# 01_-_POWER.net
KiCad netlist of a schematic drawn in Altium Designer
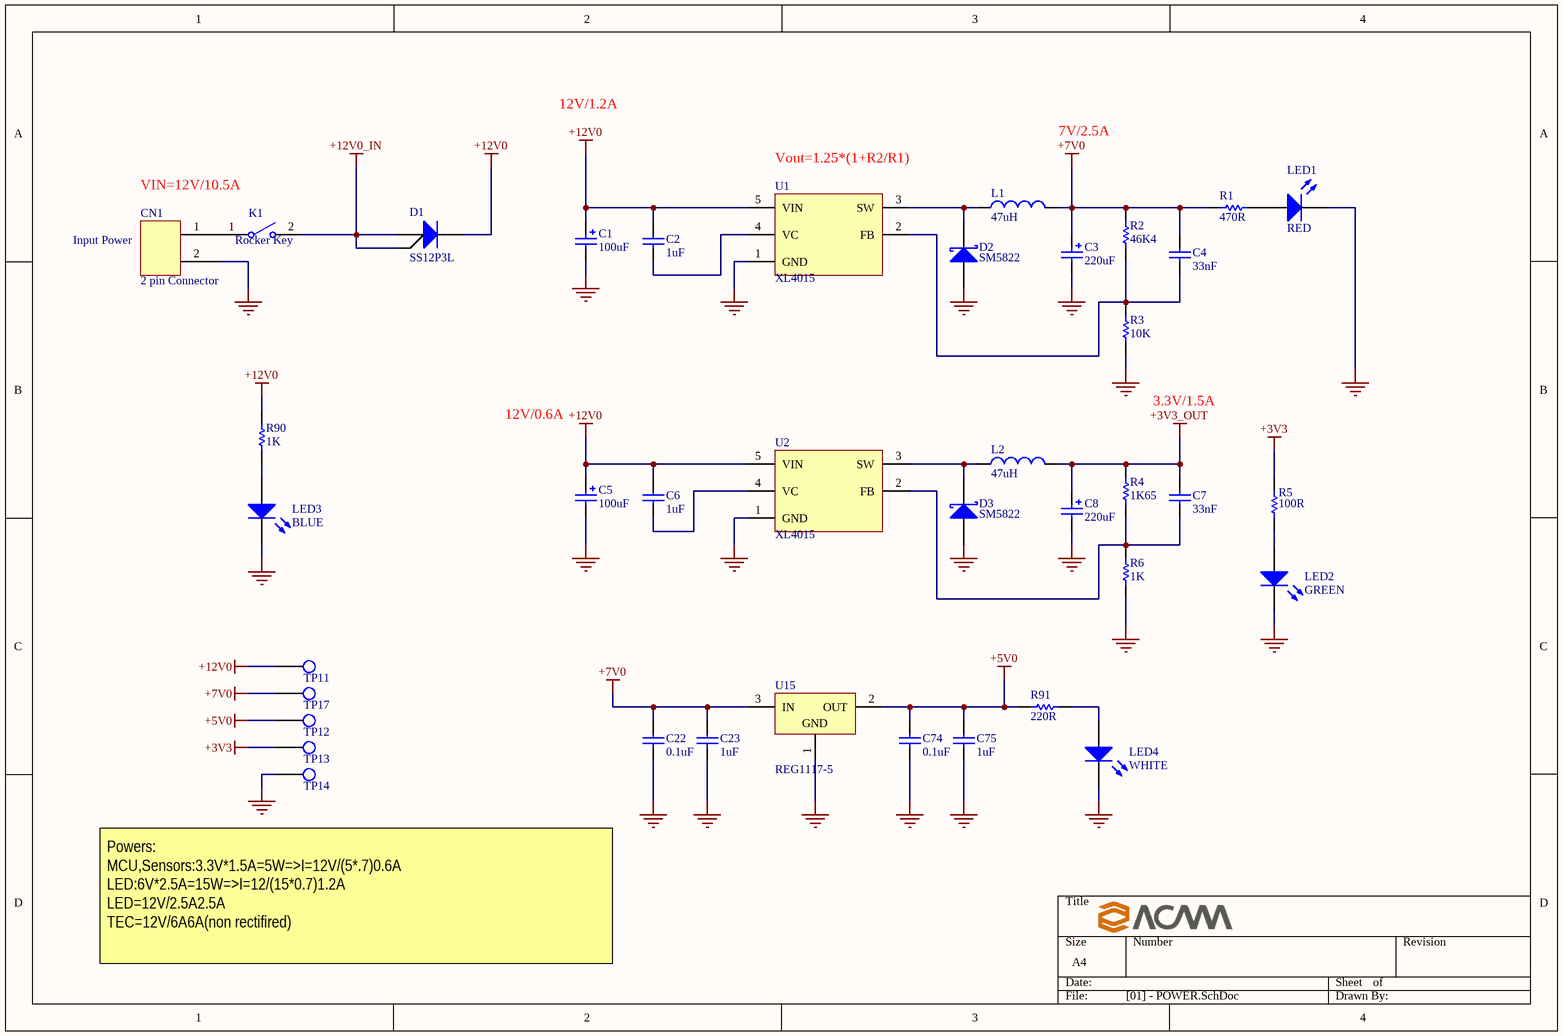
[diagram p0: [01] - POWER.SchDoc]

(export (version "E")
  (design (tool "Eeschema 10.0.6"))
  (components
    (comp (ref "C1")
      (value "100uF")
      (footprint "WCAP-ASLI_6.3x5.5")
      (description "Aluminium Electrolytic Capacitor")
      (libsource (lib "Farzan Custom Library") (part "Cap Aluminium Electrolytic"))
    )
    (comp (ref "C2")
      (value "1uF")
      (footprint "0805_C_AUTO")
      (description "Non-Pol SMD Capacitor")
      (libsource (lib "Farzan Custom Library") (part "Cap SMD"))
    )
    (comp (ref "C3")
      (value "220uF")
      (footprint "WCAP-ASLI_6.3x5.5")
      (description "Aluminium Electrolytic Capacitor")
      (libsource (lib "Farzan Custom Library") (part "Cap Aluminium Electrolytic"))
    )
    (comp (ref "C4")
      (value "33nF")
      (footprint "0805_C_AUTO")
      (description "Non-Pol SMD Capacitor")
      (libsource (lib "Farzan Custom Library") (part "Cap SMD"))
    )
    (comp (ref "C5")
      (value "100uF")
      (footprint "WCAP-ASLI_6.3x5.5")
      (description "Aluminium Electrolytic Capacitor")
      (libsource (lib "Farzan Custom Library") (part "Cap Aluminium Electrolytic"))
    )
    (comp (ref "C6")
      (value "1uF")
      (footprint "0805_C_AUTO")
      (description "Non-Pol SMD Capacitor")
      (libsource (lib "Farzan Custom Library") (part "Cap SMD"))
    )
    (comp (ref "C7")
      (value "33nF")
      (footprint "0805_C_AUTO")
      (description "Non-Pol SMD Capacitor")
      (libsource (lib "Farzan Custom Library") (part "Cap SMD"))
    )
    (comp (ref "C8")
      (value "220uF")
      (footprint "WCAP-ASLI_6.3x5.5")
      (description "Aluminium Electrolytic Capacitor")
      (libsource (lib "Farzan Custom Library") (part "Cap Aluminium Electrolytic"))
    )
    (comp (ref "C22")
      (value "0.1uF")
      (footprint "0805_C_AUTO")
      (description "Non-Pol SMD Capacitor")
      (libsource (lib "Farzan Custom Library") (part "Cap SMD"))
    )
    (comp (ref "C23")
      (value "1uF")
      (footprint "0805_C_AUTO")
      (description "Non-Pol SMD Capacitor")
      (libsource (lib "Farzan Custom Library") (part "Cap SMD"))
    )
    (comp (ref "C74")
      (value "0.1uF")
      (footprint "0805_C_AUTO")
      (description "Non-Pol SMD Capacitor")
      (libsource (lib "Farzan Custom Library") (part "Cap SMD"))
    )
    (comp (ref "C75")
      (value "1uF")
      (footprint "0805_C_AUTO")
      (description "Non-Pol SMD Capacitor")
      (libsource (lib "Farzan Custom Library") (part "Cap SMD"))
    )
    (comp (ref "CN1")
      (value "2 pin Connector")
      (footprint "KF142R_CONN_2PIN")
      (description "KAIFENG Screwless Connector 2 pin")
      (fields (field (name "MANUFACTURER PART NUM") "KF142R"))
      (libsource (lib "Farzan Custom Library") (part "Connector Screwless 2 pin"))
    )
    (comp (ref "D1")
      (value "SS12P3L")
      (footprint "TO-277A")
      (description "High Current Density Surface Mount Schottky Barrier Rectifiers")
      (fields (field (name "MANUFACTURER PART NUM") "SS12P3LHM3_A/H"))
      (libsource (lib "Farzan Custom Library") (part "Diode dual"))
    )
    (comp (ref "D2")
      (value "SM5822")
      (footprint "DO-214AB")
      (description "Schottky Diode")
      (libsource (lib "Farzan Custom Library") (part "Diode Schottky"))
    )
    (comp (ref "D3")
      (value "SM5822")
      (footprint "DO-214AB")
      (description "Schottky Diode")
      (libsource (lib "Farzan Custom Library") (part "Diode Schottky"))
    )
    (comp (ref "K1")
      (value "Rocker Key")
      (footprint "MR-1-116")
      (fields (field (name "MANUFACTURER PART NUM") "MR-1-116-C5N-BB"))
      (libsource (lib "Farzan Custom Library") (part "Rocker Key"))
    )
    (comp (ref "L1")
      (value "47uH")
      (footprint "INDUCTOR_12x12")
      (description "Inductor SMD")
      (fields (field (name "MANUFACTURER PART NUM") "MSS1210-473MED"))
      (libsource (lib "Farzan Custom Library") (part "Inductor"))
    )
    (comp (ref "L2")
      (value "47uH")
      (footprint "INDUCTOR_12x12")
      (description "Inductor SMD")
      (fields (field (name "MANUFACTURER PART NUM") "MSS1210-473MED"))
      (libsource (lib "Farzan Custom Library") (part "Inductor"))
    )
    (comp (ref "LED1")
      (value "RED")
      (footprint "LED_1206")
      (description "Typical LED")
      (libsource (lib "Farzan Custom Library") (part "LED"))
    )
    (comp (ref "LED2")
      (value "GREEN")
      (footprint "LED_1206")
      (description "Typical LED")
      (libsource (lib "Farzan Custom Library") (part "LED"))
    )
    (comp (ref "LED3")
      (value "BLUE")
      (footprint "LED_1206")
      (description "Typical LED")
      (libsource (lib "Farzan Custom Library") (part "LED"))
    )
    (comp (ref "LED4")
      (value "WHITE")
      (footprint "LED_1206")
      (description "Typical LED")
      (libsource (lib "Farzan Custom Library") (part "LED"))
    )
    (comp (ref "R1")
      (value "470R")
      (footprint "0805_R_AUTO")
      (description "SMD Resistor")
      (fields (field (name "TOLERANCE") "1%"))
      (libsource (lib "Farzan Custom Library") (part "Res SMD"))
    )
    (comp (ref "R2")
      (value "46K4")
      (footprint "0805_R_AUTO")
      (description "SMD Resistor")
      (fields (field (name "TOLERANCE") "1%"))
      (libsource (lib "Farzan Custom Library") (part "Res SMD"))
    )
    (comp (ref "R3")
      (value "10K")
      (footprint "0805_R_AUTO")
      (description "SMD Resistor")
      (fields (field (name "TOLERANCE") "1%"))
      (libsource (lib "Farzan Custom Library") (part "Res SMD"))
    )
    (comp (ref "R4")
      (value "1K65")
      (footprint "0805_R_AUTO")
      (description "SMD Resistor")
      (fields (field (name "TOLERANCE") "1%"))
      (libsource (lib "Farzan Custom Library") (part "Res SMD"))
    )
    (comp (ref "R5")
      (value "100R")
      (footprint "0805_R_AUTO")
      (description "SMD Resistor")
      (fields (field (name "TOLERANCE") "5%"))
      (libsource (lib "Farzan Custom Library") (part "Res SMD"))
    )
    (comp (ref "R6")
      (value "1K")
      (footprint "0805_R_AUTO")
      (description "SMD Resistor")
      (fields (field (name "TOLERANCE") "1%"))
      (libsource (lib "Farzan Custom Library") (part "Res SMD"))
    )
    (comp (ref "R90")
      (value "1K")
      (footprint "0805_R_AUTO")
      (description "SMD Resistor")
      (fields (field (name "TOLERANCE") "5%"))
      (libsource (lib "Farzan Custom Library") (part "Res SMD"))
    )
    (comp (ref "R91")
      (value "220R")
      (footprint "0805_R_AUTO")
      (description "SMD Resistor")
      (fields (field (name "TOLERANCE") "5%"))
      (libsource (lib "Farzan Custom Library") (part "Res SMD"))
    )
    (comp (ref "TP11")
      (value "Test Point")
      (footprint "PIN_2mm")
      (description "Test Point Footprint")
      (libsource (lib "Farzan Custom Library") (part "Test Point"))
    )
    (comp (ref "TP12")
      (value "Test Point")
      (footprint "PIN_2mm")
      (description "Test Point Footprint")
      (libsource (lib "Farzan Custom Library") (part "Test Point"))
    )
    (comp (ref "TP13")
      (value "Test Point")
      (footprint "PIN_2mm")
      (description "Test Point Footprint")
      (libsource (lib "Farzan Custom Library") (part "Test Point"))
    )
    (comp (ref "TP14")
      (value "Test Point")
      (footprint "PIN_2mm")
      (description "Test Point Footprint")
      (libsource (lib "Farzan Custom Library") (part "Test Point"))
    )
    (comp (ref "TP17")
      (value "Test Point")
      (footprint "PIN_2mm")
      (description "Test Point Footprint")
      (libsource (lib "Farzan Custom Library") (part "Test Point"))
    )
    (comp (ref "U1")
      (value "XL4015")
      (footprint "TO-263-5")
      (libsource (lib "Farzan Custom Library") (part "XL4015"))
    )
    (comp (ref "U2")
      (value "XL4015")
      (footprint "TO-263-5")
      (libsource (lib "Farzan Custom Library") (part "XL4015"))
    )
    (comp (ref "U15")
      (value "REG1117-5")
      (footprint "SOT-223")
      (description "3-Terminal Positive Fixed Voltage Regulator")
      (libsource (lib "Farzan Custom Library") (part "REG1117"))
    )
  )
  (nets
    (net (code "1") (name "+3V3") (class "Default")
      (node (ref "R5") (pin "1") (pinfunction "1_1") (pintype "passive"))
      (node (ref "TP13") (pin "1") (pinfunction "1_1") (pintype "power_in"))
    )
    (net (code "2") (name "+3V3_OUT") (class "Default")
      (node (ref "C7") (pin "2") (pinfunction "2_2") (pintype "passive"))
      (node (ref "C8") (pin "1") (pinfunction "1_1") (pintype "passive"))
      (node (ref "L2") (pin "2") (pinfunction "2_2") (pintype "passive"))
      (node (ref "R4") (pin "2") (pinfunction "2_2") (pintype "passive"))
    )
    (net (code "3") (name "+5V0") (class "Default")
      (node (ref "C74") (pin "2") (pinfunction "2_2") (pintype "passive"))
      (node (ref "C75") (pin "2") (pinfunction "2_2") (pintype "passive"))
      (node (ref "R91") (pin "1") (pinfunction "1_1") (pintype "passive"))
      (node (ref "TP12") (pin "1") (pinfunction "1_1") (pintype "power_in"))
      (node (ref "U15") (pin "2") (pinfunction "OUT_2") (pintype "power_in"))
    )
    (net (code "4") (name "+7V0") (class "Default")
      (node (ref "C22") (pin "2") (pinfunction "2_2") (pintype "passive"))
      (node (ref "C23") (pin "2") (pinfunction "2_2") (pintype "passive"))
      (node (ref "C3") (pin "1") (pinfunction "1_1") (pintype "passive"))
      (node (ref "C4") (pin "2") (pinfunction "2_2") (pintype "passive"))
      (node (ref "L1") (pin "2") (pinfunction "2_2") (pintype "passive"))
      (node (ref "R1") (pin "2") (pinfunction "2_2") (pintype "passive"))
      (node (ref "R2") (pin "2") (pinfunction "2_2") (pintype "passive"))
      (node (ref "TP17") (pin "1") (pinfunction "1_1") (pintype "power_in"))
      (node (ref "U15") (pin "3") (pinfunction "IN_3") (pintype "power_in"))
    )
    (net (code "5") (name "+12V0") (class "Default")
      (node (ref "C1") (pin "1") (pinfunction "1_1") (pintype "passive"))
      (node (ref "C2") (pin "2") (pinfunction "2_2") (pintype "passive"))
      (node (ref "C5") (pin "1") (pinfunction "1_1") (pintype "passive"))
      (node (ref "C6") (pin "2") (pinfunction "2_2") (pintype "passive"))
      (node (ref "D1") (pin "3") (pinfunction "K_3") (pintype "passive"))
      (node (ref "R90") (pin "2") (pinfunction "2_2") (pintype "passive"))
      (node (ref "TP11") (pin "1") (pinfunction "1_1") (pintype "power_in"))
      (node (ref "U1") (pin "5") (pinfunction "VIN_5") (pintype "power_in"))
      (node (ref "U2") (pin "5") (pinfunction "VIN_5") (pintype "power_in"))
    )
    (net (code "6") (name "+12V0_IN") (class "Default")
      (node (ref "D1") (pin "1") (pinfunction "A1_1") (pintype "passive"))
      (node (ref "D1") (pin "2") (pinfunction "A2_2") (pintype "passive"))
      (node (ref "K1") (pin "2") (pinfunction "NO_2") (pintype "passive"))
    )
    (net (code "7") (name "GND") (class "Default")
      (node (ref "C1") (pin "2") (pinfunction "2_2") (pintype "passive"))
      (node (ref "C22") (pin "1") (pinfunction "1_1") (pintype "passive"))
      (node (ref "C23") (pin "1") (pinfunction "1_1") (pintype "passive"))
      (node (ref "C3") (pin "2") (pinfunction "2_2") (pintype "passive"))
      (node (ref "C5") (pin "2") (pinfunction "2_2") (pintype "passive"))
      (node (ref "C74") (pin "1") (pinfunction "1_1") (pintype "passive"))
      (node (ref "C75") (pin "1") (pinfunction "1_1") (pintype "passive"))
      (node (ref "C8") (pin "2") (pinfunction "2_2") (pintype "passive"))
      (node (ref "CN1") (pin "2") (pinfunction "2_2") (pintype "passive"))
      (node (ref "D2") (pin "1") (pinfunction "A_1") (pintype "passive"))
      (node (ref "D3") (pin "1") (pinfunction "A_1") (pintype "passive"))
      (node (ref "LED1") (pin "2") (pinfunction "K_2") (pintype "passive"))
      (node (ref "LED2") (pin "2") (pinfunction "K_2") (pintype "passive"))
      (node (ref "LED3") (pin "2") (pinfunction "K_2") (pintype "passive"))
      (node (ref "LED4") (pin "2") (pinfunction "K_2") (pintype "passive"))
      (node (ref "R3") (pin "1") (pinfunction "1_1") (pintype "passive"))
      (node (ref "R6") (pin "1") (pinfunction "1_1") (pintype "passive"))
      (node (ref "TP14") (pin "1") (pinfunction "1_1") (pintype "power_in"))
      (node (ref "U1") (pin "1") (pinfunction "GND_1") (pintype "power_in"))
      (node (ref "U15") (pin "1") (pinfunction "GND_1") (pintype "power_in"))
      (node (ref "U2") (pin "1") (pinfunction "GND_1") (pintype "power_in"))
    )
    (net (code "8") (name "Net-(D2-K)") (class "Default")
      (node (ref "D2") (pin "2") (pinfunction "K_2") (pintype "passive"))
      (node (ref "L1") (pin "1") (pinfunction "1_1") (pintype "passive"))
      (node (ref "U1") (pin "3") (pinfunction "SW_3") (pintype "power_in"))
    )
    (net (code "9") (name "Net-(D3-K)") (class "Default")
      (node (ref "D3") (pin "2") (pinfunction "K_2") (pintype "passive"))
      (node (ref "L2") (pin "1") (pinfunction "1_1") (pintype "passive"))
      (node (ref "U2") (pin "3") (pinfunction "SW_3") (pintype "power_in"))
    )
    (net (code "10") (name "Net-(K1-COMMON)") (class "Default")
      (node (ref "CN1") (pin "1") (pinfunction "1_1") (pintype "passive"))
      (node (ref "K1") (pin "1") (pinfunction "COMMON_1") (pintype "passive"))
    )
    (net (code "11") (name "Net-(LED1-A)") (class "Default")
      (node (ref "LED1") (pin "1") (pinfunction "A_1") (pintype "passive"))
      (node (ref "R1") (pin "1") (pinfunction "1_1") (pintype "passive"))
    )
    (net (code "12") (name "Net-(LED2-A)") (class "Default")
      (node (ref "LED2") (pin "1") (pinfunction "A_1") (pintype "passive"))
      (node (ref "R5") (pin "2") (pinfunction "2_2") (pintype "passive"))
    )
    (net (code "13") (name "Net-(LED3-A)") (class "Default")
      (node (ref "LED3") (pin "1") (pinfunction "A_1") (pintype "passive"))
      (node (ref "R90") (pin "1") (pinfunction "1_1") (pintype "passive"))
    )
    (net (code "14") (name "Net-(LED4-A)") (class "Default")
      (node (ref "LED4") (pin "1") (pinfunction "A_1") (pintype "passive"))
      (node (ref "R91") (pin "2") (pinfunction "2_2") (pintype "passive"))
    )
    (net (code "15") (name "Net-(U1-FB)") (class "Default")
      (node (ref "C4") (pin "1") (pinfunction "1_1") (pintype "passive"))
      (node (ref "R2") (pin "1") (pinfunction "1_1") (pintype "passive"))
      (node (ref "R3") (pin "2") (pinfunction "2_2") (pintype "passive"))
      (node (ref "U1") (pin "2") (pinfunction "FB_2") (pintype "power_in"))
    )
    (net (code "16") (name "Net-(U1-VC)") (class "Default")
      (node (ref "C2") (pin "1") (pinfunction "1_1") (pintype "passive"))
      (node (ref "U1") (pin "4") (pinfunction "VC_4") (pintype "power_in"))
    )
    (net (code "17") (name "Net-(U2-FB)") (class "Default")
      (node (ref "C7") (pin "1") (pinfunction "1_1") (pintype "passive"))
      (node (ref "R4") (pin "1") (pinfunction "1_1") (pintype "passive"))
      (node (ref "R6") (pin "2") (pinfunction "2_2") (pintype "passive"))
      (node (ref "U2") (pin "2") (pinfunction "FB_2") (pintype "power_in"))
    )
    (net (code "18") (name "Net-(U2-VC)") (class "Default")
      (node (ref "C6") (pin "1") (pinfunction "1_1") (pintype "passive"))
      (node (ref "U2") (pin "4") (pinfunction "VC_4") (pintype "power_in"))
    )
  )
)
